# IMU.net
KiCad netlist of a schematic drawn in Altium Designer
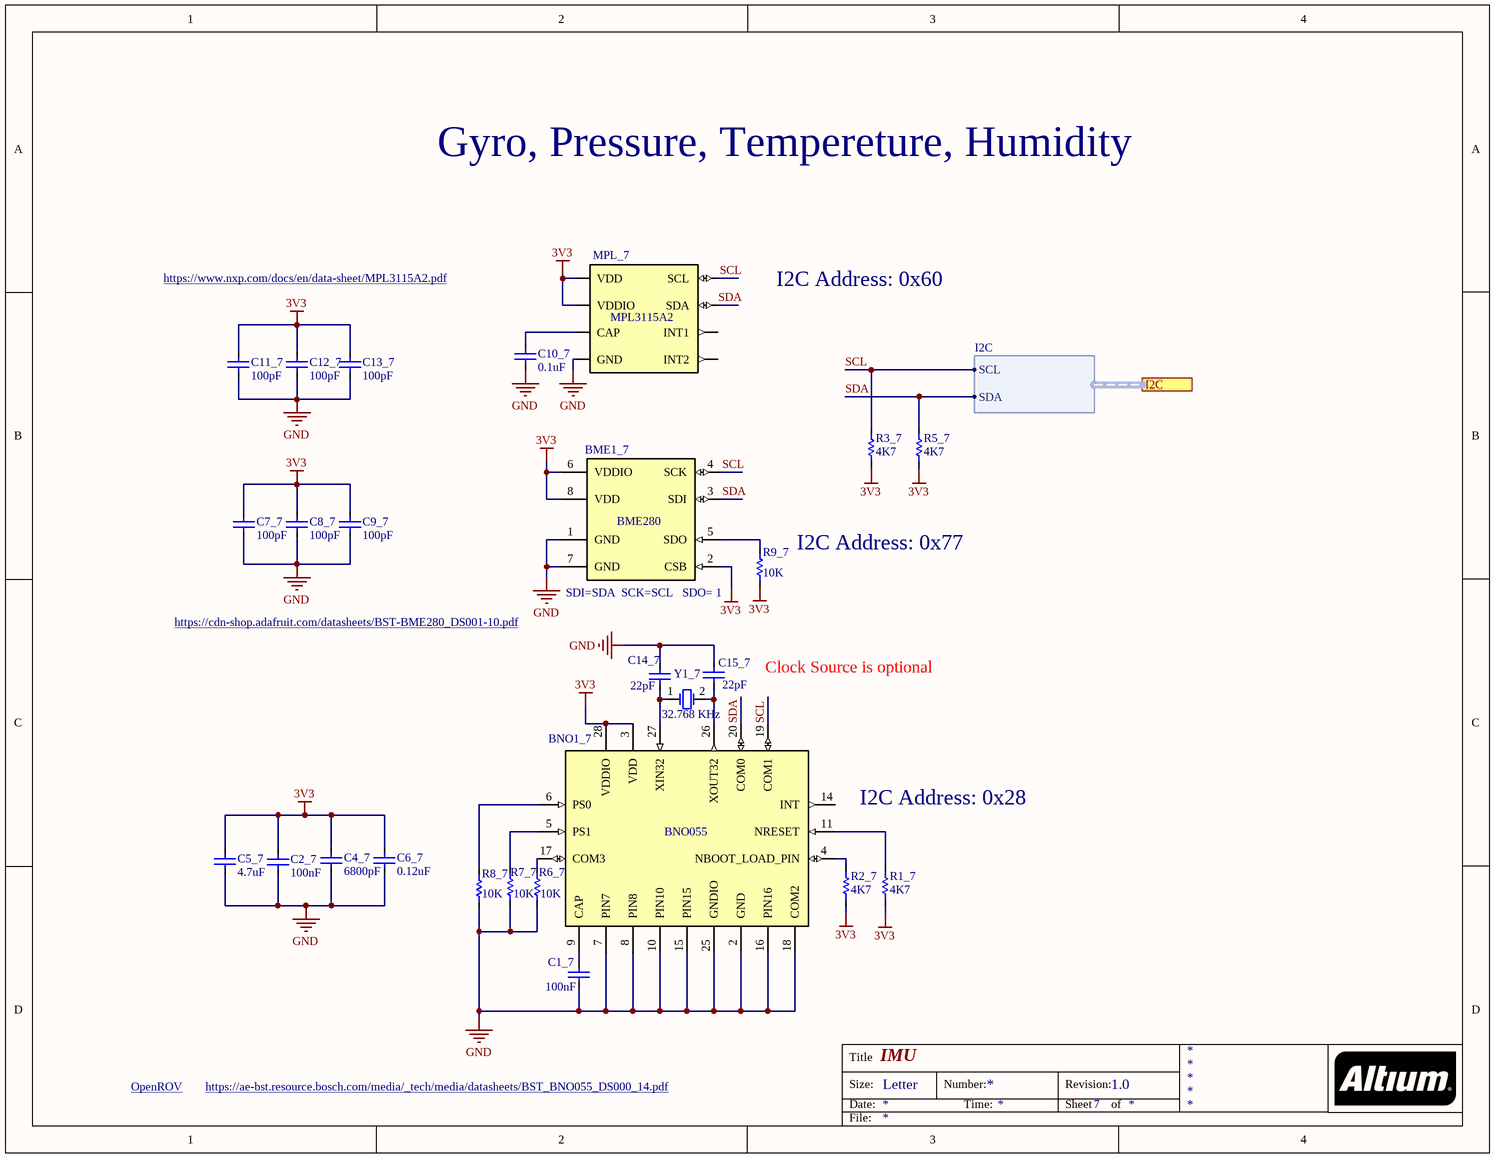
[diagram p0: IMU.SchDoc]

(export (version "E")
  (design (tool "Eeschema 10.0.6"))
  (components
    (comp (ref "BME1_7")
      (value "BME280")
      (footprint "BME280")
      (description "Integrated pressure, humidity and temperature sensor; 8-pin 2.5x2.5x0.93mm LGA")
      (fields (field (name "MF") "Bosch"))
      (libsource (lib "LaunchyRIOComponents") (part "BME280"))
    )
    (comp (ref "BNO1_7")
      (value "BNO055")
      (footprint "LGA28R50P4X10_380X520X100")
      (description "BNO055 9-axis Absolute Orientation Sensor ( SiP ) w/Sensors and Sensor Fusion")
      (fields (field (name "MF") "Bosch"))
      (libsource (lib "LaunchyRIOComponents") (part "BNO055"))
    )
    (comp (ref "C1_7")
      (value "100nF")
      (footprint "C0805C475K9RACAUTO")
      (fields (field (name "Comment") "Cap"))
      (libsource (lib "Generic_Library") (part "Cap"))
    )
    (comp (ref "C2_7")
      (value "100nF")
      (footprint "C0805C475K9RACAUTO")
      (fields (field (name "Comment") "Cap"))
      (libsource (lib "Generic_Library") (part "Cap"))
    )
    (comp (ref "C4_7")
      (value "6800pF")
      (footprint "C0805C475K9RACAUTO")
      (fields (field (name "Comment") "Cap"))
      (libsource (lib "Generic_Library") (part "Cap"))
    )
    (comp (ref "C5_7")
      (value "4.7uF")
      (footprint "C0805C475K9RACAUTO")
      (fields (field (name "Comment") "Cap"))
      (libsource (lib "Generic_Library") (part "Cap"))
    )
    (comp (ref "C6_7")
      (value "0.12uF")
      (footprint "C0805C475K9RACAUTO")
      (fields (field (name "Comment") "Cap"))
      (libsource (lib "Generic_Library") (part "Cap"))
    )
    (comp (ref "C7_7")
      (value "100pF")
      (footprint "C0805C475K9RACAUTO")
      (fields (field (name "Comment") "Cap"))
      (libsource (lib "Generic_Library") (part "Cap"))
    )
    (comp (ref "C8_7")
      (value "100pF")
      (footprint "C0805C475K9RACAUTO")
      (fields (field (name "Comment") "Cap"))
      (libsource (lib "Generic_Library") (part "Cap"))
    )
    (comp (ref "C9_7")
      (value "100pF")
      (footprint "C0805C475K9RACAUTO")
      (fields (field (name "Comment") "Cap"))
      (libsource (lib "Generic_Library") (part "Cap"))
    )
    (comp (ref "C10_7")
      (value "0.1uF")
      (footprint "C0805C475K9RACAUTO")
      (fields (field (name "Comment") "Cap"))
      (libsource (lib "Generic_Library") (part "Cap"))
    )
    (comp (ref "C11_7")
      (value "100pF")
      (footprint "C0805C475K9RACAUTO")
      (fields (field (name "Comment") "Cap"))
      (libsource (lib "Generic_Library") (part "Cap"))
    )
    (comp (ref "C12_7")
      (value "100pF")
      (footprint "C0805C475K9RACAUTO")
      (fields (field (name "Comment") "Cap"))
      (libsource (lib "Generic_Library") (part "Cap"))
    )
    (comp (ref "C13_7")
      (value "100pF")
      (footprint "C0805C475K9RACAUTO")
      (fields (field (name "Comment") "Cap"))
      (libsource (lib "Generic_Library") (part "Cap"))
    )
    (comp (ref "C14_7")
      (value "22pF")
      (footprint "C0805C475K9RACAUTO")
      (fields (field (name "Comment") "Cap"))
      (libsource (lib "Generic_Library") (part "Cap"))
    )
    (comp (ref "C15_7")
      (value "22pF")
      (footprint "C0805C475K9RACAUTO")
      (fields (field (name "Comment") "Cap"))
      (libsource (lib "Generic_Library") (part "Cap"))
    )
    (comp (ref "MPL_7")
      (value "MPL3115A2")
      (footprint "LGA8")
      (description "Pressure Sensor, 50-110kpa, Lga-8")
      (fields (field (name "MF") "NXP Semiconductors"))
      (libsource (lib "LaunchyRIOComponents") (part "MPL3115A2"))
    )
    (comp (ref "R1_7")
      (value "4K7")
      (footprint "SMD Resistors:RES 0805")
      (fields (field (name "Comment") "Res"))
      (libsource (lib "Generic_Library") (part "Res"))
    )
    (comp (ref "R2_7")
      (value "4K7")
      (footprint "SMD Resistors:RES 0805")
      (fields (field (name "Comment") "Res"))
      (libsource (lib "Generic_Library") (part "Res"))
    )
    (comp (ref "R3_7")
      (value "4K7")
      (footprint "SMD Resistors:RES 0805")
      (fields (field (name "Comment") "Res"))
      (libsource (lib "Generic_Library") (part "Res"))
    )
    (comp (ref "R5_7")
      (value "4K7")
      (footprint "SMD Resistors:RES 0805")
      (fields (field (name "Comment") "Res"))
      (libsource (lib "Generic_Library") (part "Res"))
    )
    (comp (ref "R6_7")
      (value "10K")
      (footprint "SMD Resistors:RES 0805")
      (fields (field (name "Comment") "Res"))
      (libsource (lib "Generic_Library") (part "Res"))
    )
    (comp (ref "R7_7")
      (value "10K")
      (footprint "SMD Resistors:RES 0805")
      (fields (field (name "Comment") "Res"))
      (libsource (lib "Generic_Library") (part "Res"))
    )
    (comp (ref "R8_7")
      (value "10K")
      (footprint "SMD Resistors:RES 0805")
      (fields (field (name "Comment") "Res"))
      (libsource (lib "Generic_Library") (part "Res"))
    )
    (comp (ref "R9_7")
      (value "10K")
      (footprint "SMD Resistors:RES 0805")
      (fields (field (name "Comment") "Res"))
      (libsource (lib "Generic_Library") (part "Res"))
    )
    (comp (ref "Y1_7")
      (value "32.768 KHz")
      (footprint "FC-135R 32.7680KA-A3")
      (fields (field (name "Comment") "16MHz"))
      (libsource (lib "Generic_Library") (part "XTAL"))
    )
  )
  (nets
    (net (code "2") (name "/SCL") (class "Default")
      (node (ref "BME1_7") (pin "4") (pinfunction "SCK_4") (pintype "bidirectional"))
      (node (ref "BNO1_7") (pin "19") (pinfunction "COM1_19") (pintype "bidirectional"))
      (node (ref "MPL_7") (pin "8") (pinfunction "SCL_8") (pintype "bidirectional"))
      (node (ref "R3_7") (pin "2") (pinfunction "2_2") (pintype "passive"))
    )
    (net (code "3") (name "/SDA") (class "Default")
      (node (ref "BME1_7") (pin "3") (pinfunction "SDI_3") (pintype "bidirectional"))
      (node (ref "BNO1_7") (pin "20") (pinfunction "COM0_20") (pintype "bidirectional"))
      (node (ref "MPL_7") (pin "7") (pinfunction "SDA_7") (pintype "bidirectional"))
      (node (ref "R5_7") (pin "2") (pinfunction "2_2") (pintype "passive"))
    )
    (net (code "5") (name "3V3") (class "Default")
      (node (ref "BME1_7") (pin "2") (pinfunction "CSB_2") (pintype "input"))
      (node (ref "BME1_7") (pin "6") (pinfunction "VDDIO_6") (pintype "power_in"))
      (node (ref "BME1_7") (pin "8") (pinfunction "VDD_8") (pintype "power_in"))
      (node (ref "BNO1_7") (pin "28") (pinfunction "VDDIO_28") (pintype "power_in"))
      (node (ref "BNO1_7") (pin "3") (pinfunction "VDD_3") (pintype "power_in"))
      (node (ref "C11_7") (pin "2") (pinfunction "2_2") (pintype "passive"))
      (node (ref "C12_7") (pin "2") (pinfunction "2_2") (pintype "passive"))
      (node (ref "C13_7") (pin "2") (pinfunction "2_2") (pintype "passive"))
      (node (ref "C2_7") (pin "2") (pinfunction "2_2") (pintype "passive"))
      (node (ref "C4_7") (pin "2") (pinfunction "2_2") (pintype "passive"))
      (node (ref "C5_7") (pin "2") (pinfunction "2_2") (pintype "passive"))
      (node (ref "C6_7") (pin "2") (pinfunction "2_2") (pintype "passive"))
      (node (ref "C7_7") (pin "2") (pinfunction "2_2") (pintype "passive"))
      (node (ref "C8_7") (pin "2") (pinfunction "2_2") (pintype "passive"))
      (node (ref "C9_7") (pin "2") (pinfunction "2_2") (pintype "passive"))
      (node (ref "MPL_7") (pin "1") (pinfunction "VDD_1") (pintype "power_in"))
      (node (ref "MPL_7") (pin "4") (pinfunction "VDDIO_4") (pintype "power_in"))
      (node (ref "R1_7") (pin "1") (pinfunction "1_1") (pintype "passive"))
      (node (ref "R2_7") (pin "1") (pinfunction "1_1") (pintype "passive"))
      (node (ref "R3_7") (pin "1") (pinfunction "1_1") (pintype "passive"))
      (node (ref "R5_7") (pin "1") (pinfunction "1_1") (pintype "passive"))
      (node (ref "R9_7") (pin "1") (pinfunction "1_1") (pintype "passive"))
    )
    (net (code "6") (name "GND") (class "Default")
      (node (ref "BME1_7") (pin "1") (pinfunction "GND_1") (pintype "power_in"))
      (node (ref "BME1_7") (pin "7") (pinfunction "GND_7") (pintype "power_in"))
      (node (ref "BNO1_7") (pin "10") (pinfunction "PIN10_10") (pintype "power_in"))
      (node (ref "BNO1_7") (pin "15") (pinfunction "PIN15_15") (pintype "power_in"))
      (node (ref "BNO1_7") (pin "16") (pinfunction "PIN16_16") (pintype "power_in"))
      (node (ref "BNO1_7") (pin "18") (pinfunction "COM2_18") (pintype "passive"))
      (node (ref "BNO1_7") (pin "2") (pinfunction "GND_2") (pintype "power_in"))
      (node (ref "BNO1_7") (pin "25") (pinfunction "GNDIO_25") (pintype "power_in"))
      (node (ref "BNO1_7") (pin "7") (pinfunction "PIN7_7") (pintype "passive"))
      (node (ref "BNO1_7") (pin "8") (pinfunction "PIN8_8") (pintype "passive"))
      (node (ref "C10_7") (pin "1") (pinfunction "1_1") (pintype "passive"))
      (node (ref "C11_7") (pin "1") (pinfunction "1_1") (pintype "passive"))
      (node (ref "C12_7") (pin "1") (pinfunction "1_1") (pintype "passive"))
      (node (ref "C13_7") (pin "1") (pinfunction "1_1") (pintype "passive"))
      (node (ref "C14_7") (pin "1") (pinfunction "1_1") (pintype "passive"))
      (node (ref "C15_7") (pin "1") (pinfunction "1_1") (pintype "passive"))
      (node (ref "C1_7") (pin "1") (pinfunction "1_1") (pintype "passive"))
      (node (ref "C2_7") (pin "1") (pinfunction "1_1") (pintype "passive"))
      (node (ref "C4_7") (pin "1") (pinfunction "1_1") (pintype "passive"))
      (node (ref "C5_7") (pin "1") (pinfunction "1_1") (pintype "passive"))
      (node (ref "C6_7") (pin "1") (pinfunction "1_1") (pintype "passive"))
      (node (ref "C7_7") (pin "1") (pinfunction "1_1") (pintype "passive"))
      (node (ref "C8_7") (pin "1") (pinfunction "1_1") (pintype "passive"))
      (node (ref "C9_7") (pin "1") (pinfunction "1_1") (pintype "passive"))
      (node (ref "MPL_7") (pin "3") (pinfunction "GND_3") (pintype "power_in"))
      (node (ref "R6_7") (pin "1") (pinfunction "1_1") (pintype "passive"))
      (node (ref "R7_7") (pin "1") (pinfunction "1_1") (pintype "passive"))
      (node (ref "R8_7") (pin "1") (pinfunction "1_1") (pintype "passive"))
    )
    (net (code "7") (name "Net-(BME1_7-SDO)") (class "Default")
      (node (ref "BME1_7") (pin "5") (pinfunction "SDO_5") (pintype "input"))
      (node (ref "R9_7") (pin "2") (pinfunction "2_2") (pintype "passive"))
    )
    (net (code "8") (name "Net-(BNO1_7-CAP)") (class "Default")
      (node (ref "BNO1_7") (pin "9") (pinfunction "CAP_9") (pintype "passive"))
      (node (ref "C1_7") (pin "2") (pinfunction "2_2") (pintype "passive"))
    )
    (net (code "9") (name "Net-(BNO1_7-COM3)") (class "Default")
      (node (ref "BNO1_7") (pin "17") (pinfunction "COM3_17") (pintype "bidirectional"))
      (node (ref "R6_7") (pin "2") (pinfunction "2_2") (pintype "passive"))
    )
    (net (code "10") (name "Net-(BNO1_7-NBOOT_LOAD_PIN)") (class "Default")
      (node (ref "BNO1_7") (pin "4") (pinfunction "NBOOT_LOAD_PIN_4") (pintype "bidirectional"))
      (node (ref "R2_7") (pin "2") (pinfunction "2_2") (pintype "passive"))
    )
    (net (code "11") (name "Net-(BNO1_7-NRESET)") (class "Default")
      (node (ref "BNO1_7") (pin "11") (pinfunction "NRESET_11") (pintype "input"))
      (node (ref "R1_7") (pin "2") (pinfunction "2_2") (pintype "passive"))
    )
    (net (code "12") (name "Net-(BNO1_7-PS0)") (class "Default")
      (node (ref "BNO1_7") (pin "6") (pinfunction "PS0_6") (pintype "input"))
      (node (ref "R8_7") (pin "2") (pinfunction "2_2") (pintype "passive"))
    )
    (net (code "13") (name "Net-(BNO1_7-PS1)") (class "Default")
      (node (ref "BNO1_7") (pin "5") (pinfunction "PS1_5") (pintype "input"))
      (node (ref "R7_7") (pin "2") (pinfunction "2_2") (pintype "passive"))
    )
    (net (code "14") (name "Net-(BNO1_7-XIN32)") (class "Default")
      (node (ref "BNO1_7") (pin "27") (pinfunction "XIN32_27") (pintype "input"))
      (node (ref "C14_7") (pin "2") (pinfunction "2_2") (pintype "passive"))
      (node (ref "Y1_7") (pin "1") (pinfunction "OSC1_1") (pintype "passive"))
    )
    (net (code "15") (name "Net-(BNO1_7-XOUT32)") (class "Default")
      (node (ref "BNO1_7") (pin "26") (pinfunction "XOUT32_26") (pintype "output"))
      (node (ref "C15_7") (pin "2") (pinfunction "2_2") (pintype "passive"))
      (node (ref "Y1_7") (pin "2") (pinfunction "OSC2_2") (pintype "passive"))
    )
    (net (code "16") (name "Net-(MPL_7-CAP)") (class "Default")
      (node (ref "C10_7") (pin "2") (pinfunction "2_2") (pintype "passive"))
      (node (ref "MPL_7") (pin "2") (pinfunction "CAP_2") (pintype "power_in"))
    )
    (net (code "17") (name "unconnected-(BNO1_7-INT-Pad14)") (class "Default")
      (node (ref "BNO1_7") (pin "14") (pinfunction "INT_14") (pintype "output"))
    )
    (net (code "18") (name "unconnected-(MPL_7-INT1-Pad6)") (class "Default")
      (node (ref "MPL_7") (pin "6") (pinfunction "INT1_6") (pintype "output"))
    )
    (net (code "19") (name "unconnected-(MPL_7-INT2-Pad5)") (class "Default")
      (node (ref "MPL_7") (pin "5") (pinfunction "INT2_5") (pintype "output"))
    )
  )
)
